# Triangular.net
KiCad netlist of a schematic drawn in Altium Designer
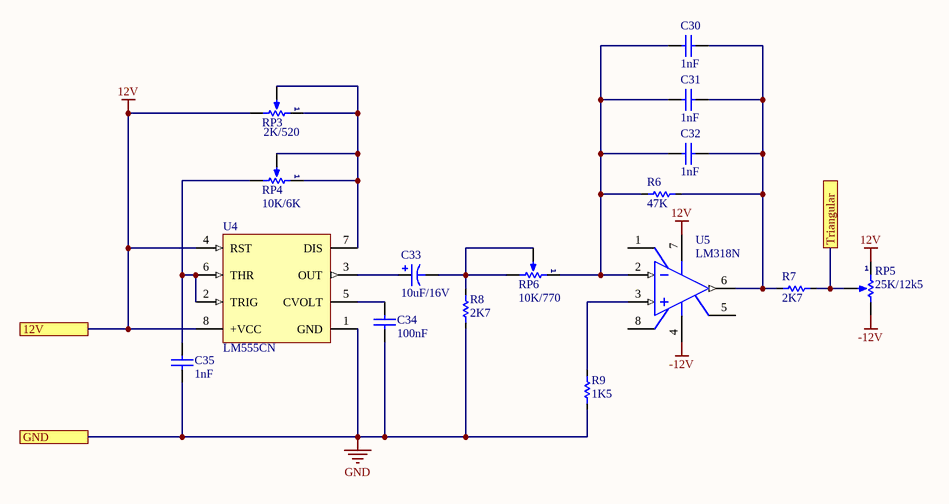
[diagram p0: Triangular.SchDoc]

(export (version "E")
  (design (tool "Eeschema 10.0.6"))
  (components
    (comp (ref "C30")
      (value "Cap Ceramico Disco")
      (footprint "CAP DISCO 200mil")
      (description "Capacitor Ceramico de Insercion")
      (fields (field (name "VALOR") "1nF"))
      (libsource (lib "RUF-Dispositivos-Grales") (part "Cap Ceramico Disco"))
    )
    (comp (ref "C31")
      (value "Cap Ceramico Disco")
      (footprint "CAP DISCO 200mil")
      (description "Capacitor Ceramico de Insercion")
      (fields (field (name "VALOR") "1nF"))
      (libsource (lib "RUF-Dispositivos-Grales") (part "Cap Ceramico Disco"))
    )
    (comp (ref "C32")
      (value "Cap Ceramico Disco")
      (footprint "CAP DISCO 200mil")
      (description "Capacitor Ceramico de Insercion")
      (fields (field (name "VALOR") "1nF"))
      (libsource (lib "RUF-Dispositivos-Grales") (part "Cap Ceramico Disco"))
    )
    (comp (ref "C33")
      (value "Cap Electrolitico Radial")
      (footprint "CAPR D250 H450 R100 mil")
      (description "Cap Electrolitico de insercion")
      (fields (field (name "VALOR") "10uF/16V"))
      (libsource (lib "RUF-Dispositivos-Grales") (part "Cap Electrolitico Radial"))
    )
    (comp (ref "C34")
      (value "Cap Ceramico Disco")
      (footprint "RAD-0.3")
      (description "Capacitor Ceramico de Insercion")
      (fields (field (name "VALOR") "100nF"))
      (libsource (lib "RUF-Dispositivos-Grales") (part "Cap Ceramico Disco"))
    )
    (comp (ref "C35")
      (value "Cap Ceramico Disco")
      (footprint "CAP DISCO 200mil")
      (description "Capacitor Ceramico de Insercion")
      (fields (field (name "VALOR") "1nF"))
      (libsource (lib "RUF-Dispositivos-Grales") (part "Cap Ceramico Disco"))
    )
    (comp (ref "R6")
      (value "Res SMD")
      (footprint "1206 resistor")
      (description "Res Smd")
      (fields (field (name "VALOR") "47K"))
      (libsource (lib "RUF-Dispositivos-Grales") (part "Res SMD"))
    )
    (comp (ref "R7")
      (value "Res SMD")
      (footprint "1206 resistor")
      (description "Res Smd")
      (fields (field (name "VALOR") "2K7"))
      (libsource (lib "RUF-Dispositivos-Grales") (part "Res SMD"))
    )
    (comp (ref "R8")
      (value "Res SMD")
      (footprint "1206 resistor")
      (description "Res Smd")
      (fields (field (name "VALOR") "2K7"))
      (libsource (lib "RUF-Dispositivos-Grales") (part "Res SMD"))
    )
    (comp (ref "R9")
      (value "Res SMD")
      (footprint "1206 resistor")
      (description "Res Smd")
      (fields (field (name "VALOR") "1K5"))
      (libsource (lib "RUF-Dispositivos-Grales") (part "Res SMD"))
    )
    (comp (ref "RP3")
      (value "Trimpot")
      (footprint "Trimpot Multivuelta Vertical")
      (description "Preset")
      (fields (field (name "VALOR") "2K/520"))
      (libsource (lib "RUF-Dispositivos-Grales") (part "Trimpot"))
    )
    (comp (ref "RP4")
      (value "Trimpot")
      (footprint "Trimpot Multivuelta Vertical")
      (description "Preset")
      (fields (field (name "VALOR") "10K/6K"))
      (libsource (lib "RUF-Dispositivos-Grales") (part "Trimpot"))
    )
    (comp (ref "RP5")
      (value "Trimpot")
      (footprint "Trimpot Multivuelta Vertical")
      (description "Preset")
      (fields (field (name "VALOR") "25K/12k5"))
      (libsource (lib "RUF-Dispositivos-Grales") (part "Trimpot"))
    )
    (comp (ref "RP6")
      (value "Trimpot")
      (footprint "Trimpot Multivuelta Vertical")
      (description "Preset")
      (fields (field (name "VALOR") "10K/770"))
      (libsource (lib "RUF-Dispositivos-Grales") (part "Trimpot"))
    )
    (comp (ref "U4")
      (value "LM555CN")
      (footprint "N08E")
      (description "Timer, 8-pin MDIP")
      (fields
        (field (name "MANUFACTURER") "National Semiconductor")
        (field (name "PUBLISHER") "Altium Limited")
      )
      (libsource (lib "NSC Analog") (part "LM555CN"))
    )
    (comp (ref "U5")
      (value "LM318N")
      (footprint "DIP-8")
      (description "Operational Amplifier, 8-pin MDIP")
      (fields
        (field (name "MANUFACTURER") "National Semiconductor")
        (field (name "PUBLISHER") "Altium Limited")
      )
      (libsource (lib "NSC Amplifier") (part "LM318N"))
    )
  )
  (nets
    (net (code "1") (name "-12V") (class "Default")
      (node (ref "RP5") (pin "2") (pinfunction "BOT_2") (pintype "passive"))
      (node (ref "U5") (pin "4") (pinfunction "V-_4") (pintype "power_in"))
    )
    (net (code "2") (name "/Triangular") (class "Default")
      (node (ref "R7") (pin "1") (pinfunction "1_1") (pintype "passive"))
      (node (ref "RP5") (pin "3") (pinfunction "TAP_3") (pintype "passive"))
    )
    (net (code "3") (name "12V") (class "Default")
      (node (ref "RP3") (pin "2") (pinfunction "BOT_2") (pintype "passive"))
      (node (ref "RP5") (pin "1") (pinfunction "TOP_1") (pintype "passive"))
      (node (ref "U4") (pin "4") (pinfunction "RST_4") (pintype "input"))
      (node (ref "U4") (pin "8") (pinfunction "+VCC_8") (pintype "power_in"))
      (node (ref "U5") (pin "7") (pinfunction "V+_7") (pintype "power_in"))
    )
    (net (code "4") (name "GND") (class "Default")
      (node (ref "C34") (pin "1") (pinfunction "1_1") (pintype "passive"))
      (node (ref "C35") (pin "1") (pinfunction "1_1") (pintype "passive"))
      (node (ref "R8") (pin "1") (pinfunction "1_1") (pintype "passive"))
      (node (ref "R9") (pin "1") (pinfunction "1_1") (pintype "passive"))
      (node (ref "U4") (pin "1") (pinfunction "GND_1") (pintype "power_in"))
    )
    (net (code "5") (name "Net-(RP3-TAP)") (class "Default")
      (node (ref "RP3") (pin "1") (pinfunction "TOP_1") (pintype "passive"))
      (node (ref "RP3") (pin "3") (pinfunction "TAP_3") (pintype "passive"))
      (node (ref "RP4") (pin "1") (pinfunction "TOP_1") (pintype "passive"))
      (node (ref "RP4") (pin "3") (pinfunction "TAP_3") (pintype "passive"))
      (node (ref "U4") (pin "7") (pinfunction "DIS_7") (pintype "open_collector"))
    )
    (net (code "6") (name "Net-(RP4-BOT)") (class "Default")
      (node (ref "C35") (pin "2") (pinfunction "2_2") (pintype "passive"))
      (node (ref "RP4") (pin "2") (pinfunction "BOT_2") (pintype "passive"))
      (node (ref "U4") (pin "2") (pinfunction "TRIG_2") (pintype "input"))
      (node (ref "U4") (pin "6") (pinfunction "THR_6") (pintype "input"))
    )
    (net (code "7") (name "Net-(RP6-BOT)") (class "Default")
      (node (ref "C33") (pin "2") (pinfunction "2_2") (pintype "passive"))
      (node (ref "R8") (pin "2") (pinfunction "2_2") (pintype "passive"))
      (node (ref "RP6") (pin "2") (pinfunction "BOT_2") (pintype "passive"))
      (node (ref "RP6") (pin "3") (pinfunction "TAP_3") (pintype "passive"))
    )
    (net (code "8") (name "Net-(RP6-TOP)") (class "Default")
      (node (ref "C30") (pin "2") (pinfunction "2_2") (pintype "passive"))
      (node (ref "C31") (pin "2") (pinfunction "2_2") (pintype "passive"))
      (node (ref "C32") (pin "2") (pinfunction "2_2") (pintype "passive"))
      (node (ref "R6") (pin "2") (pinfunction "2_2") (pintype "passive"))
      (node (ref "RP6") (pin "1") (pinfunction "TOP_1") (pintype "passive"))
      (node (ref "U5") (pin "2") (pinfunction "IN-_2") (pintype "input"))
    )
    (net (code "9") (name "Net-(U4-CVOLT)") (class "Default")
      (node (ref "C34") (pin "2") (pinfunction "2_2") (pintype "passive"))
      (node (ref "U4") (pin "5") (pinfunction "CVOLT_5") (pintype "passive"))
    )
    (net (code "10") (name "Net-(U4-OUT)") (class "Default")
      (node (ref "C33") (pin "1") (pinfunction "1_1") (pintype "passive"))
      (node (ref "U4") (pin "3") (pinfunction "OUT_3") (pintype "output"))
    )
    (net (code "11") (name "Net-(U5-IN+)") (class "Default")
      (node (ref "R9") (pin "2") (pinfunction "2_2") (pintype "passive"))
      (node (ref "U5") (pin "3") (pinfunction "IN+_3") (pintype "input"))
    )
    (net (code "12") (name "Net-(U5-OUT)") (class "Default")
      (node (ref "C30") (pin "1") (pinfunction "1_1") (pintype "passive"))
      (node (ref "C31") (pin "1") (pinfunction "1_1") (pintype "passive"))
      (node (ref "C32") (pin "1") (pinfunction "1_1") (pintype "passive"))
      (node (ref "R6") (pin "1") (pinfunction "1_1") (pintype "passive"))
      (node (ref "R7") (pin "2") (pinfunction "2_2") (pintype "passive"))
      (node (ref "U5") (pin "6") (pinfunction "OUT_6") (pintype "output"))
    )
    (net (code "13") (name "unconnected-(U5-BAL{slash}COMP1-Pad1)") (class "Default")
      (node (ref "U5") (pin "1") (pinfunction "BAL/COMP1_1") (pintype "passive"))
    )
    (net (code "14") (name "unconnected-(U5-BAL{slash}COMP3-Pad5)") (class "Default")
      (node (ref "U5") (pin "5") (pinfunction "BAL/COMP3_5") (pintype "passive"))
    )
    (net (code "15") (name "unconnected-(U5-COMP2-Pad8)") (class "Default")
      (node (ref "U5") (pin "8") (pinfunction "COMP2_8") (pintype "passive"))
    )
  )
)
